# f28069_interfacing.net
KiCad netlist of a schematic drawn in EAGLE
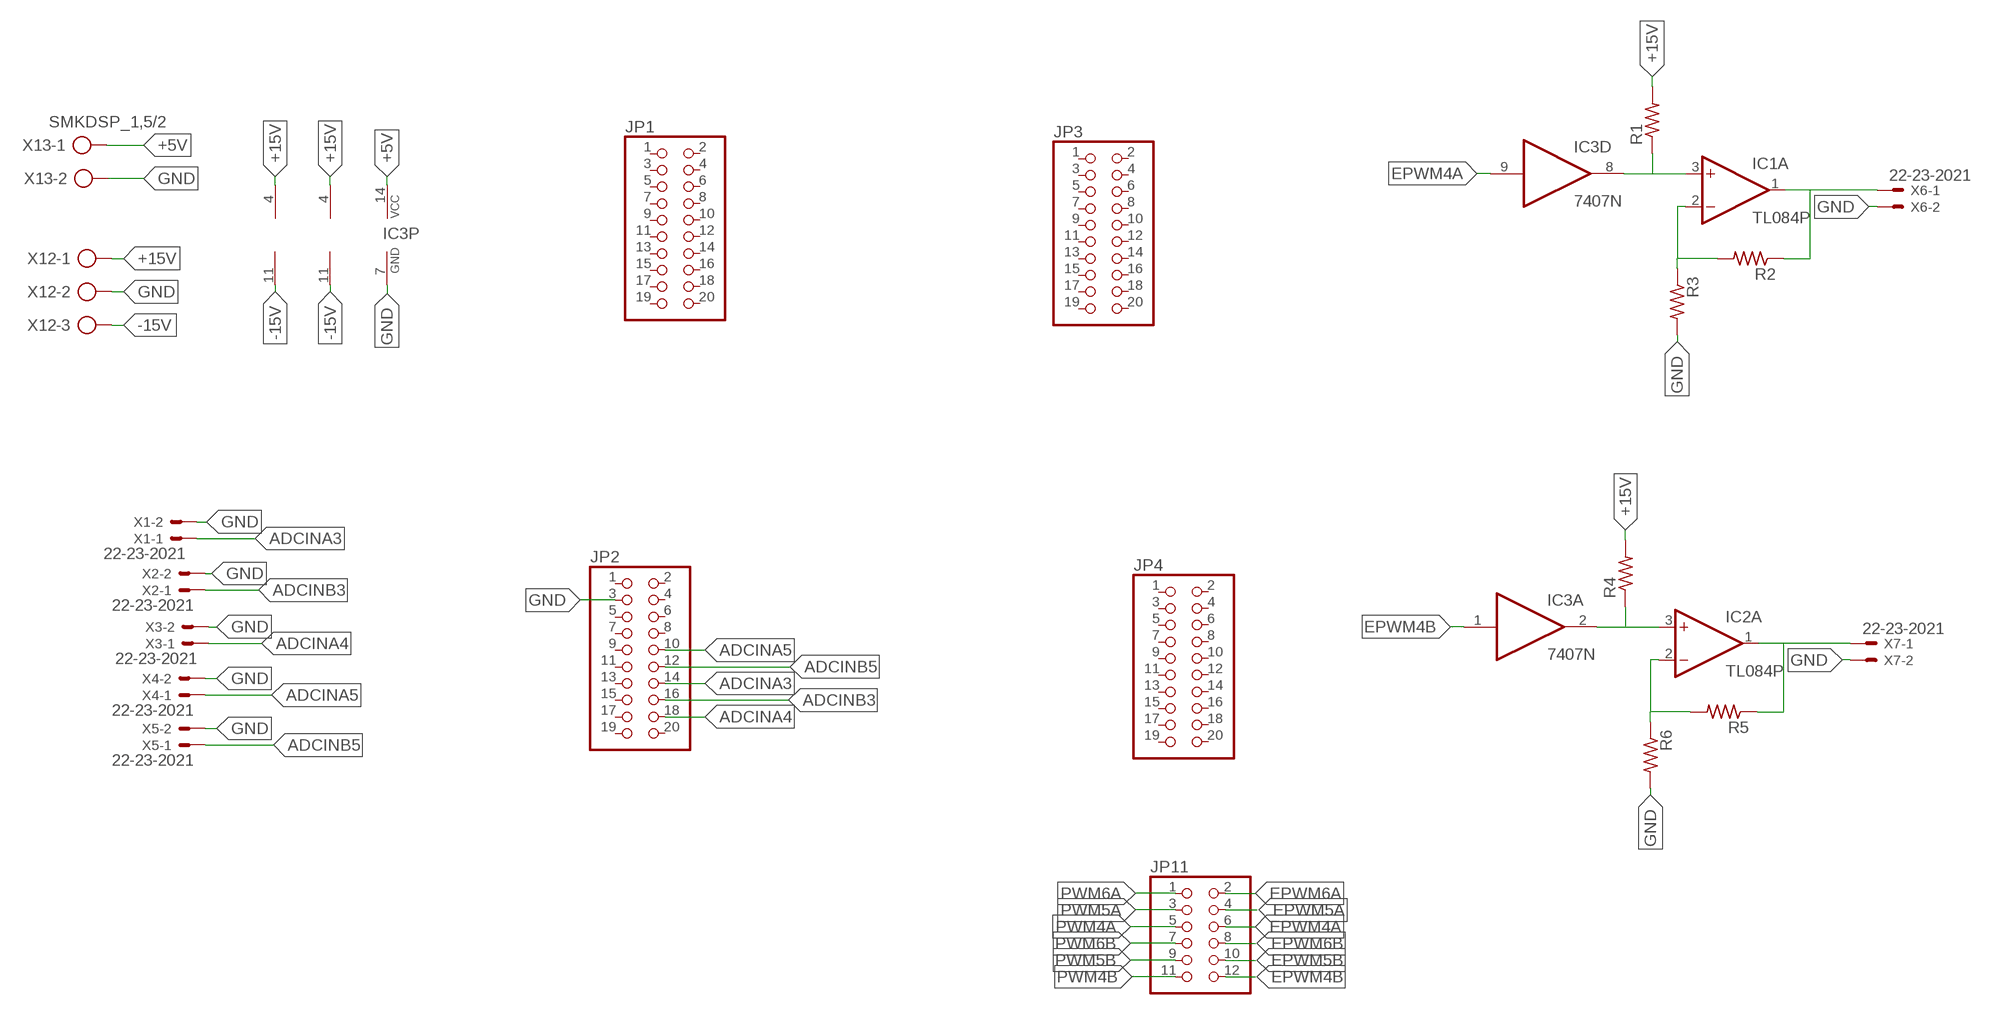
[diagram p0: schematic, sheet 1, part 1 of 2]
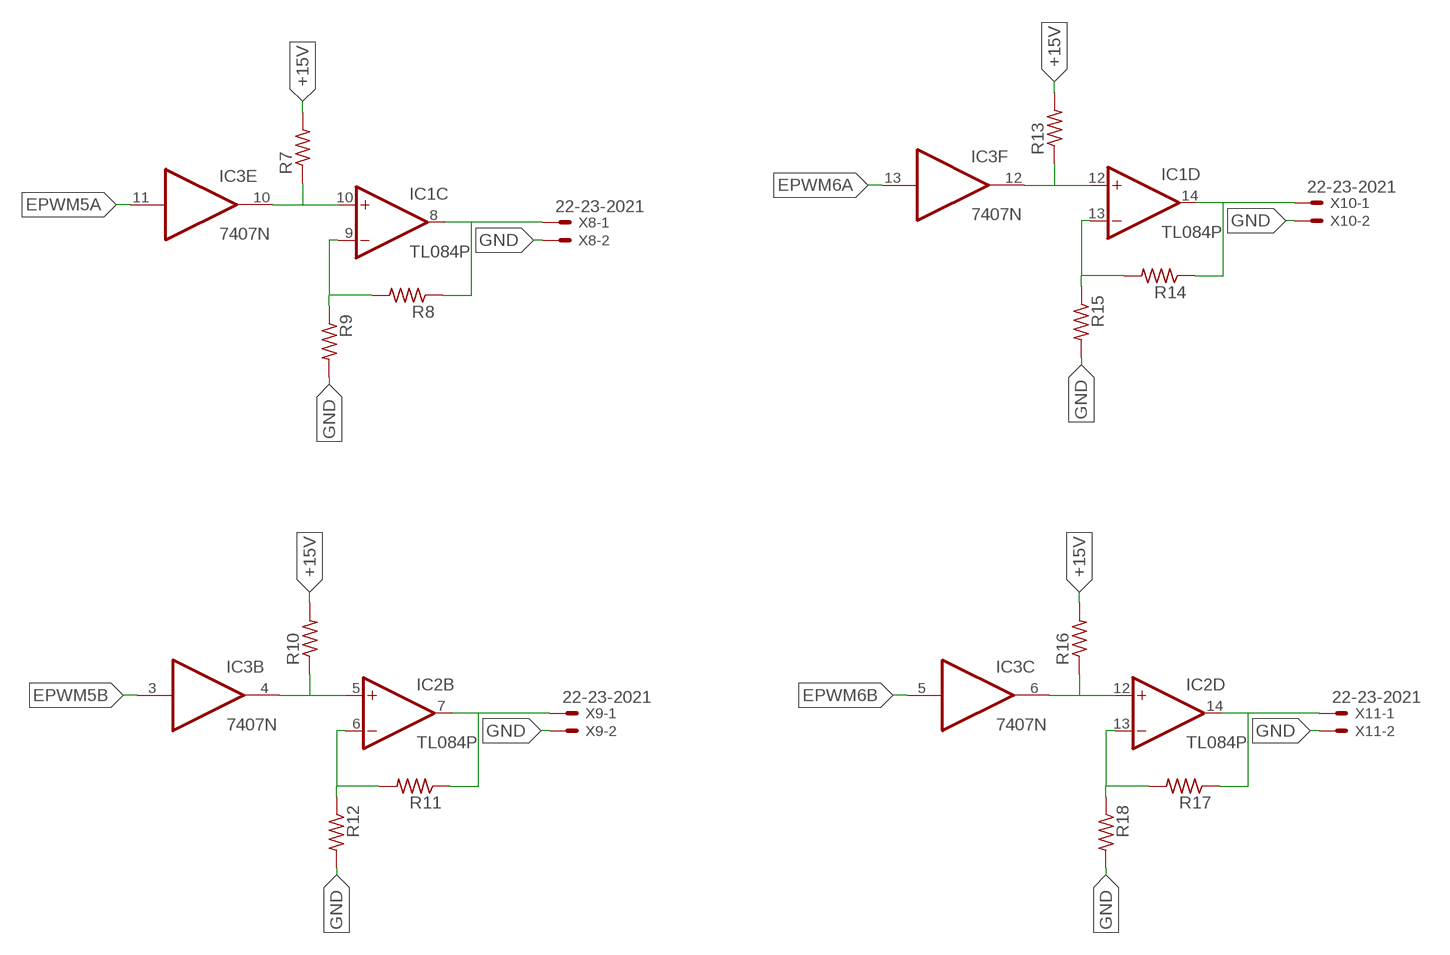
[diagram p1: schematic, sheet 1, part 2 of 2]

(export (version "E")
  (design (tool "Eeschema 10.0.6"))
  (components
    (comp (ref "IC1")
      (value "TL084P")
      (footprint "eagle-import:DIL14")
      (libsource (lib "eagle-import") (part "TL084P"))
    )
    (comp (ref "IC2")
      (value "TL084P")
      (footprint "eagle-import:DIL14")
      (libsource (lib "eagle-import") (part "TL084P"))
    )
    (comp (ref "IC3")
      (value "7407N")
      (footprint "eagle-import:DIL14")
      (libsource (lib "eagle-import") (part "7407N"))
    )
    (comp (ref "JP1")
      (value "PINHD-2X10")
      (footprint "eagle-import:2X10")
      (libsource (lib "eagle-import") (part "PINHD-2X10"))
    )
    (comp (ref "JP2")
      (value "PINHD-2X10")
      (footprint "eagle-import:2X10")
      (libsource (lib "eagle-import") (part "PINHD-2X10"))
    )
    (comp (ref "JP3")
      (value "PINHD-2X10")
      (footprint "eagle-import:2X10")
      (libsource (lib "eagle-import") (part "PINHD-2X10"))
    )
    (comp (ref "JP4")
      (value "PINHD-2X10")
      (footprint "eagle-import:2X10")
      (libsource (lib "eagle-import") (part "PINHD-2X10"))
    )
    (comp (ref "JP11")
      (value "PINHD-2X6")
      (footprint "eagle-import:2X06")
      (libsource (lib "eagle-import") (part "PINHD-2X6"))
    )
    (comp (ref "R1")
      (value "R-US_0207/10")
      (footprint "eagle-import:0207_10")
      (libsource (lib "eagle-import") (part "R-US_0207/10"))
    )
    (comp (ref "R2")
      (value "R-US_0207/10")
      (footprint "eagle-import:0207_10")
      (libsource (lib "eagle-import") (part "R-US_0207/10"))
    )
    (comp (ref "R3")
      (value "R-US_0207/10")
      (footprint "eagle-import:0207_10")
      (libsource (lib "eagle-import") (part "R-US_0207/10"))
    )
    (comp (ref "R4")
      (value "R-US_0207/10")
      (footprint "eagle-import:0207_10")
      (libsource (lib "eagle-import") (part "R-US_0207/10"))
    )
    (comp (ref "R5")
      (value "R-US_0207/10")
      (footprint "eagle-import:0207_10")
      (libsource (lib "eagle-import") (part "R-US_0207/10"))
    )
    (comp (ref "R6")
      (value "R-US_0207/10")
      (footprint "eagle-import:0207_10")
      (libsource (lib "eagle-import") (part "R-US_0207/10"))
    )
    (comp (ref "R7")
      (value "R-US_0207/10")
      (footprint "eagle-import:0207_10")
      (libsource (lib "eagle-import") (part "R-US_0207/10"))
    )
    (comp (ref "R8")
      (value "R-US_0207/10")
      (footprint "eagle-import:0207_10")
      (libsource (lib "eagle-import") (part "R-US_0207/10"))
    )
    (comp (ref "R9")
      (value "R-US_0207/10")
      (footprint "eagle-import:0207_10")
      (libsource (lib "eagle-import") (part "R-US_0207/10"))
    )
    (comp (ref "R10")
      (value "R-US_0207/10")
      (footprint "eagle-import:0207_10")
      (libsource (lib "eagle-import") (part "R-US_0207/10"))
    )
    (comp (ref "R11")
      (value "R-US_0207/10")
      (footprint "eagle-import:0207_10")
      (libsource (lib "eagle-import") (part "R-US_0207/10"))
    )
    (comp (ref "R12")
      (value "R-US_0207/10")
      (footprint "eagle-import:0207_10")
      (libsource (lib "eagle-import") (part "R-US_0207/10"))
    )
    (comp (ref "R13")
      (value "R-US_0207/10")
      (footprint "eagle-import:0207_10")
      (libsource (lib "eagle-import") (part "R-US_0207/10"))
    )
    (comp (ref "R14")
      (value "R-US_0207/10")
      (footprint "eagle-import:0207_10")
      (libsource (lib "eagle-import") (part "R-US_0207/10"))
    )
    (comp (ref "R15")
      (value "R-US_0207/10")
      (footprint "eagle-import:0207_10")
      (libsource (lib "eagle-import") (part "R-US_0207/10"))
    )
    (comp (ref "R16")
      (value "R-US_0207/10")
      (footprint "eagle-import:0207_10")
      (libsource (lib "eagle-import") (part "R-US_0207/10"))
    )
    (comp (ref "R17")
      (value "R-US_0207/10")
      (footprint "eagle-import:0207_10")
      (libsource (lib "eagle-import") (part "R-US_0207/10"))
    )
    (comp (ref "R18")
      (value "R-US_0207/10")
      (footprint "eagle-import:0207_10")
      (libsource (lib "eagle-import") (part "R-US_0207/10"))
    )
    (comp (ref "X1")
      (value "22-23-2021")
      (footprint "eagle-import:22-23-2021")
      (fields (field (name "MF") "MOLEX"))
      (libsource (lib "eagle-import") (part "22-23-2021"))
    )
    (comp (ref "X2")
      (value "22-23-2021")
      (footprint "eagle-import:22-23-2021")
      (fields (field (name "MF") "MOLEX"))
      (libsource (lib "eagle-import") (part "22-23-2021"))
    )
    (comp (ref "X3")
      (value "22-23-2021")
      (footprint "eagle-import:22-23-2021")
      (fields (field (name "MF") "MOLEX"))
      (libsource (lib "eagle-import") (part "22-23-2021"))
    )
    (comp (ref "X4")
      (value "22-23-2021")
      (footprint "eagle-import:22-23-2021")
      (fields (field (name "MF") "MOLEX"))
      (libsource (lib "eagle-import") (part "22-23-2021"))
    )
    (comp (ref "X5")
      (value "22-23-2021")
      (footprint "eagle-import:22-23-2021")
      (fields (field (name "MF") "MOLEX"))
      (libsource (lib "eagle-import") (part "22-23-2021"))
    )
    (comp (ref "X6")
      (value "22-23-2021")
      (footprint "eagle-import:22-23-2021")
      (fields (field (name "MF") "MOLEX"))
      (libsource (lib "eagle-import") (part "22-23-2021"))
    )
    (comp (ref "X7")
      (value "22-23-2021")
      (footprint "eagle-import:22-23-2021")
      (fields (field (name "MF") "MOLEX"))
      (libsource (lib "eagle-import") (part "22-23-2021"))
    )
    (comp (ref "X8")
      (value "22-23-2021")
      (footprint "eagle-import:22-23-2021")
      (fields (field (name "MF") "MOLEX"))
      (libsource (lib "eagle-import") (part "22-23-2021"))
    )
    (comp (ref "X9")
      (value "22-23-2021")
      (footprint "eagle-import:22-23-2021")
      (fields (field (name "MF") "MOLEX"))
      (libsource (lib "eagle-import") (part "22-23-2021"))
    )
    (comp (ref "X10")
      (value "22-23-2021")
      (footprint "eagle-import:22-23-2021")
      (fields (field (name "MF") "MOLEX"))
      (libsource (lib "eagle-import") (part "22-23-2021"))
    )
    (comp (ref "X11")
      (value "22-23-2021")
      (footprint "eagle-import:22-23-2021")
      (fields (field (name "MF") "MOLEX"))
      (libsource (lib "eagle-import") (part "22-23-2021"))
    )
    (comp (ref "X12")
      (value "AK300/3")
      (footprint "eagle-import:AK300_3")
      (libsource (lib "eagle-import") (part "AK300/3"))
    )
    (comp (ref "X13")
      (value "SMKDSP_1,5/2")
      (footprint "eagle-import:SMKDSP_1,5_2")
      (fields (field (name "MF") "FARNELL") (field (name "MPN") "1733570"))
      (libsource (lib "eagle-import") (part "SMKDSP_1,5/2"))
    )
  )
  (nets
    (net (code "1") (name "+5V") (class "Default")
      (node (ref "IC3") (pin "14") (pinfunction "VCC_14") (pintype "power_in"))
      (node (ref "X13") (pin "1") (pinfunction "KL_1") (pintype "passive"))
    )
    (net (code "2") (name "+15V") (class "Default")
      (node (ref "IC1") (pin "4") (pinfunction "V+_4") (pintype "power_in"))
      (node (ref "IC2") (pin "4") (pinfunction "V+_4") (pintype "power_in"))
      (node (ref "R1") (pin "2") (pinfunction "2_2") (pintype "passive"))
      (node (ref "R10") (pin "2") (pinfunction "2_2") (pintype "passive"))
      (node (ref "R13") (pin "2") (pinfunction "2_2") (pintype "passive"))
      (node (ref "R16") (pin "2") (pinfunction "2_2") (pintype "passive"))
      (node (ref "R4") (pin "2") (pinfunction "2_2") (pintype "passive"))
      (node (ref "R7") (pin "2") (pinfunction "2_2") (pintype "passive"))
      (node (ref "X12") (pin "1") (pinfunction "KL_1") (pintype "passive"))
    )
    (net (code "3") (name "-15V") (class "Default")
      (node (ref "IC1") (pin "11") (pinfunction "V-_11") (pintype "power_in"))
      (node (ref "IC2") (pin "11") (pinfunction "V-_11") (pintype "power_in"))
      (node (ref "X12") (pin "3") (pinfunction "KL_3") (pintype "passive"))
    )
    (net (code "4") (name "ADCINA3") (class "Default")
      (node (ref "JP2") (pin "14") (pinfunction "14_14") (pintype "passive"))
      (node (ref "X1") (pin "1") (pinfunction "S_1") (pintype "passive"))
    )
    (net (code "5") (name "ADCINA4") (class "Default")
      (node (ref "JP2") (pin "18") (pinfunction "18_18") (pintype "passive"))
      (node (ref "X3") (pin "1") (pinfunction "S_1") (pintype "passive"))
    )
    (net (code "6") (name "ADCINA5") (class "Default")
      (node (ref "JP2") (pin "10") (pinfunction "10_10") (pintype "passive"))
      (node (ref "X4") (pin "1") (pinfunction "S_1") (pintype "passive"))
    )
    (net (code "7") (name "ADCINB3") (class "Default")
      (node (ref "JP2") (pin "16") (pinfunction "16_16") (pintype "passive"))
      (node (ref "X2") (pin "1") (pinfunction "S_1") (pintype "passive"))
    )
    (net (code "8") (name "ADCINB5") (class "Default")
      (node (ref "JP2") (pin "12") (pinfunction "12_12") (pintype "passive"))
      (node (ref "X5") (pin "1") (pinfunction "S_1") (pintype "passive"))
    )
    (net (code "9") (name "EPWM4A") (class "Default")
      (node (ref "IC3") (pin "9") (pinfunction "I_9") (pintype "input"))
      (node (ref "JP11") (pin "6") (pinfunction "6_6") (pintype "passive"))
    )
    (net (code "10") (name "EPWM4B") (class "Default")
      (node (ref "IC3") (pin "1") (pinfunction "I_1") (pintype "input"))
      (node (ref "JP11") (pin "12") (pinfunction "12_12") (pintype "passive"))
    )
    (net (code "11") (name "EPWM5A") (class "Default")
      (node (ref "IC3") (pin "11") (pinfunction "I_11") (pintype "input"))
      (node (ref "JP11") (pin "4") (pinfunction "4_4") (pintype "passive"))
    )
    (net (code "12") (name "EPWM5B") (class "Default")
      (node (ref "IC3") (pin "3") (pinfunction "I_3") (pintype "input"))
      (node (ref "JP11") (pin "10") (pinfunction "10_10") (pintype "passive"))
    )
    (net (code "13") (name "EPWM6A") (class "Default")
      (node (ref "IC3") (pin "13") (pinfunction "I_13") (pintype "input"))
      (node (ref "JP11") (pin "2") (pinfunction "2_2") (pintype "passive"))
    )
    (net (code "14") (name "EPWM6B") (class "Default")
      (node (ref "IC3") (pin "5") (pinfunction "I_5") (pintype "input"))
      (node (ref "JP11") (pin "8") (pinfunction "8_8") (pintype "passive"))
    )
    (net (code "15") (name "GND") (class "Default")
      (node (ref "IC3") (pin "7") (pinfunction "GND_7") (pintype "power_in"))
      (node (ref "JP2") (pin "3") (pinfunction "3_3") (pintype "passive"))
      (node (ref "R12") (pin "2") (pinfunction "2_2") (pintype "passive"))
      (node (ref "R15") (pin "2") (pinfunction "2_2") (pintype "passive"))
      (node (ref "R18") (pin "2") (pinfunction "2_2") (pintype "passive"))
      (node (ref "R3") (pin "2") (pinfunction "2_2") (pintype "passive"))
      (node (ref "R6") (pin "2") (pinfunction "2_2") (pintype "passive"))
      (node (ref "R9") (pin "2") (pinfunction "2_2") (pintype "passive"))
      (node (ref "X1") (pin "2") (pinfunction "S_2") (pintype "passive"))
      (node (ref "X10") (pin "2") (pinfunction "S_2") (pintype "passive"))
      (node (ref "X11") (pin "2") (pinfunction "S_2") (pintype "passive"))
      (node (ref "X12") (pin "2") (pinfunction "KL_2") (pintype "passive"))
      (node (ref "X13") (pin "2") (pinfunction "KL_2") (pintype "passive"))
      (node (ref "X2") (pin "2") (pinfunction "S_2") (pintype "passive"))
      (node (ref "X3") (pin "2") (pinfunction "S_2") (pintype "passive"))
      (node (ref "X4") (pin "2") (pinfunction "S_2") (pintype "passive"))
      (node (ref "X5") (pin "2") (pinfunction "S_2") (pintype "passive"))
      (node (ref "X6") (pin "2") (pinfunction "S_2") (pintype "passive"))
      (node (ref "X7") (pin "2") (pinfunction "S_2") (pintype "passive"))
      (node (ref "X8") (pin "2") (pinfunction "S_2") (pintype "passive"))
      (node (ref "X9") (pin "2") (pinfunction "S_2") (pintype "passive"))
    )
    (net (code "16") (name "Net-(IC1A-+IN)") (class "Default")
      (node (ref "IC1") (pin "3") (pinfunction "+IN_3") (pintype "input"))
      (node (ref "IC3") (pin "8") (pinfunction "O_8") (pintype "open_collector"))
      (node (ref "R1") (pin "1") (pinfunction "1_1") (pintype "passive"))
    )
    (net (code "17") (name "Net-(IC1A--IN)") (class "Default")
      (node (ref "IC1") (pin "2") (pinfunction "-IN_2") (pintype "input"))
      (node (ref "R2") (pin "2") (pinfunction "2_2") (pintype "passive"))
      (node (ref "R3") (pin "1") (pinfunction "1_1") (pintype "passive"))
    )
    (net (code "18") (name "Net-(IC1A-OUT)") (class "Default")
      (node (ref "IC1") (pin "1") (pinfunction "OUT_1") (pintype "output"))
      (node (ref "R2") (pin "1") (pinfunction "1_1") (pintype "passive"))
      (node (ref "X6") (pin "1") (pinfunction "S_1") (pintype "passive"))
    )
    (net (code "19") (name "Net-(IC1C-+IN)") (class "Default")
      (node (ref "IC1") (pin "10") (pinfunction "+IN_10") (pintype "input"))
      (node (ref "IC3") (pin "10") (pinfunction "O_10") (pintype "open_collector"))
      (node (ref "R7") (pin "1") (pinfunction "1_1") (pintype "passive"))
    )
    (net (code "20") (name "Net-(IC1C--IN)") (class "Default")
      (node (ref "IC1") (pin "9") (pinfunction "-IN_9") (pintype "input"))
      (node (ref "R8") (pin "2") (pinfunction "2_2") (pintype "passive"))
      (node (ref "R9") (pin "1") (pinfunction "1_1") (pintype "passive"))
    )
    (net (code "21") (name "Net-(IC1C-OUT)") (class "Default")
      (node (ref "IC1") (pin "8") (pinfunction "OUT_8") (pintype "output"))
      (node (ref "R8") (pin "1") (pinfunction "1_1") (pintype "passive"))
      (node (ref "X8") (pin "1") (pinfunction "S_1") (pintype "passive"))
    )
    (net (code "22") (name "Net-(IC1D-+IN)") (class "Default")
      (node (ref "IC1") (pin "12") (pinfunction "+IN_12") (pintype "input"))
      (node (ref "IC3") (pin "12") (pinfunction "O_12") (pintype "open_collector"))
      (node (ref "R13") (pin "1") (pinfunction "1_1") (pintype "passive"))
    )
    (net (code "23") (name "Net-(IC1D--IN)") (class "Default")
      (node (ref "IC1") (pin "13") (pinfunction "-IN_13") (pintype "input"))
      (node (ref "R14") (pin "2") (pinfunction "2_2") (pintype "passive"))
      (node (ref "R15") (pin "1") (pinfunction "1_1") (pintype "passive"))
    )
    (net (code "24") (name "Net-(IC1D-OUT)") (class "Default")
      (node (ref "IC1") (pin "14") (pinfunction "OUT_14") (pintype "output"))
      (node (ref "R14") (pin "1") (pinfunction "1_1") (pintype "passive"))
      (node (ref "X10") (pin "1") (pinfunction "S_1") (pintype "passive"))
    )
    (net (code "25") (name "Net-(IC2A-+IN)") (class "Default")
      (node (ref "IC2") (pin "3") (pinfunction "+IN_3") (pintype "input"))
      (node (ref "IC3") (pin "2") (pinfunction "O_2") (pintype "open_collector"))
      (node (ref "R4") (pin "1") (pinfunction "1_1") (pintype "passive"))
    )
    (net (code "26") (name "Net-(IC2A--IN)") (class "Default")
      (node (ref "IC2") (pin "2") (pinfunction "-IN_2") (pintype "input"))
      (node (ref "R5") (pin "2") (pinfunction "2_2") (pintype "passive"))
      (node (ref "R6") (pin "1") (pinfunction "1_1") (pintype "passive"))
    )
    (net (code "27") (name "Net-(IC2A-OUT)") (class "Default")
      (node (ref "IC2") (pin "1") (pinfunction "OUT_1") (pintype "output"))
      (node (ref "R5") (pin "1") (pinfunction "1_1") (pintype "passive"))
      (node (ref "X7") (pin "1") (pinfunction "S_1") (pintype "passive"))
    )
    (net (code "28") (name "Net-(IC2B-+IN)") (class "Default")
      (node (ref "IC2") (pin "5") (pinfunction "+IN_5") (pintype "input"))
      (node (ref "IC3") (pin "4") (pinfunction "O_4") (pintype "open_collector"))
      (node (ref "R10") (pin "1") (pinfunction "1_1") (pintype "passive"))
    )
    (net (code "29") (name "Net-(IC2B--IN)") (class "Default")
      (node (ref "IC2") (pin "6") (pinfunction "-IN_6") (pintype "input"))
      (node (ref "R11") (pin "2") (pinfunction "2_2") (pintype "passive"))
      (node (ref "R12") (pin "1") (pinfunction "1_1") (pintype "passive"))
    )
    (net (code "30") (name "Net-(IC2B-OUT)") (class "Default")
      (node (ref "IC2") (pin "7") (pinfunction "OUT_7") (pintype "output"))
      (node (ref "R11") (pin "1") (pinfunction "1_1") (pintype "passive"))
      (node (ref "X9") (pin "1") (pinfunction "S_1") (pintype "passive"))
    )
    (net (code "31") (name "Net-(IC2D-+IN)") (class "Default")
      (node (ref "IC2") (pin "12") (pinfunction "+IN_12") (pintype "input"))
      (node (ref "IC3") (pin "6") (pinfunction "O_6") (pintype "open_collector"))
      (node (ref "R16") (pin "1") (pinfunction "1_1") (pintype "passive"))
    )
    (net (code "32") (name "Net-(IC2D--IN)") (class "Default")
      (node (ref "IC2") (pin "13") (pinfunction "-IN_13") (pintype "input"))
      (node (ref "R17") (pin "2") (pinfunction "2_2") (pintype "passive"))
      (node (ref "R18") (pin "1") (pinfunction "1_1") (pintype "passive"))
    )
    (net (code "33") (name "Net-(IC2D-OUT)") (class "Default")
      (node (ref "IC2") (pin "14") (pinfunction "OUT_14") (pintype "output"))
      (node (ref "R17") (pin "1") (pinfunction "1_1") (pintype "passive"))
      (node (ref "X11") (pin "1") (pinfunction "S_1") (pintype "passive"))
    )
    (net (code "34") (name "PWM4A") (class "Default")
      (node (ref "JP11") (pin "5") (pinfunction "5_5") (pintype "passive"))
    )
    (net (code "35") (name "PWM4B") (class "Default")
      (node (ref "JP11") (pin "11") (pinfunction "11_11") (pintype "passive"))
    )
    (net (code "36") (name "PWM5A") (class "Default")
      (node (ref "JP11") (pin "3") (pinfunction "3_3") (pintype "passive"))
    )
    (net (code "37") (name "PWM5B") (class "Default")
      (node (ref "JP11") (pin "9") (pinfunction "9_9") (pintype "passive"))
    )
    (net (code "38") (name "PWM6A") (class "Default")
      (node (ref "JP11") (pin "1") (pinfunction "1_1") (pintype "passive"))
    )
    (net (code "39") (name "PWM6B") (class "Default")
      (node (ref "JP11") (pin "7") (pinfunction "7_7") (pintype "passive"))
    )
    (net (code "40") (name "unconnected-(JP1-Pad1)") (class "Default")
      (node (ref "JP1") (pin "1") (pinfunction "1_1") (pintype "passive"))
    )
    (net (code "41") (name "unconnected-(JP1-Pad2)") (class "Default")
      (node (ref "JP1") (pin "2") (pinfunction "2_2") (pintype "passive"))
    )
    (net (code "42") (name "unconnected-(JP1-Pad3)") (class "Default")
      (node (ref "JP1") (pin "3") (pinfunction "3_3") (pintype "passive"))
    )
    (net (code "43") (name "unconnected-(JP1-Pad4)") (class "Default")
      (node (ref "JP1") (pin "4") (pinfunction "4_4") (pintype "passive"))
    )
    (net (code "44") (name "unconnected-(JP1-Pad5)") (class "Default")
      (node (ref "JP1") (pin "5") (pinfunction "5_5") (pintype "passive"))
    )
    (net (code "45") (name "unconnected-(JP1-Pad6)") (class "Default")
      (node (ref "JP1") (pin "6") (pinfunction "6_6") (pintype "passive"))
    )
    (net (code "46") (name "unconnected-(JP1-Pad7)") (class "Default")
      (node (ref "JP1") (pin "7") (pinfunction "7_7") (pintype "passive"))
    )
    (net (code "47") (name "unconnected-(JP1-Pad8)") (class "Default")
      (node (ref "JP1") (pin "8") (pinfunction "8_8") (pintype "passive"))
    )
    (net (code "48") (name "unconnected-(JP1-Pad9)") (class "Default")
      (node (ref "JP1") (pin "9") (pinfunction "9_9") (pintype "passive"))
    )
    (net (code "49") (name "unconnected-(JP1-Pad10)") (class "Default")
      (node (ref "JP1") (pin "10") (pinfunction "10_10") (pintype "passive"))
    )
    (net (code "50") (name "unconnected-(JP1-Pad11)") (class "Default")
      (node (ref "JP1") (pin "11") (pinfunction "11_11") (pintype "passive"))
    )
    (net (code "51") (name "unconnected-(JP1-Pad12)") (class "Default")
      (node (ref "JP1") (pin "12") (pinfunction "12_12") (pintype "passive"))
    )
    (net (code "52") (name "unconnected-(JP1-Pad13)") (class "Default")
      (node (ref "JP1") (pin "13") (pinfunction "13_13") (pintype "passive"))
    )
    (net (code "53") (name "unconnected-(JP1-Pad14)") (class "Default")
      (node (ref "JP1") (pin "14") (pinfunction "14_14") (pintype "passive"))
    )
    (net (code "54") (name "unconnected-(JP1-Pad15)") (class "Default")
      (node (ref "JP1") (pin "15") (pinfunction "15_15") (pintype "passive"))
    )
    (net (code "55") (name "unconnected-(JP1-Pad16)") (class "Default")
      (node (ref "JP1") (pin "16") (pinfunction "16_16") (pintype "passive"))
    )
    (net (code "56") (name "unconnected-(JP1-Pad17)") (class "Default")
      (node (ref "JP1") (pin "17") (pinfunction "17_17") (pintype "passive"))
    )
    (net (code "57") (name "unconnected-(JP1-Pad18)") (class "Default")
      (node (ref "JP1") (pin "18") (pinfunction "18_18") (pintype "passive"))
    )
    (net (code "58") (name "unconnected-(JP1-Pad19)") (class "Default")
      (node (ref "JP1") (pin "19") (pinfunction "19_19") (pintype "passive"))
    )
    (net (code "59") (name "unconnected-(JP1-Pad20)") (class "Default")
      (node (ref "JP1") (pin "20") (pinfunction "20_20") (pintype "passive"))
    )
    (net (code "60") (name "unconnected-(JP2-Pad1)") (class "Default")
      (node (ref "JP2") (pin "1") (pinfunction "1_1") (pintype "passive"))
    )
    (net (code "61") (name "unconnected-(JP2-Pad2)") (class "Default")
      (node (ref "JP2") (pin "2") (pinfunction "2_2") (pintype "passive"))
    )
    (net (code "62") (name "unconnected-(JP2-Pad4)") (class "Default")
      (node (ref "JP2") (pin "4") (pinfunction "4_4") (pintype "passive"))
    )
    (net (code "63") (name "unconnected-(JP2-Pad5)") (class "Default")
      (node (ref "JP2") (pin "5") (pinfunction "5_5") (pintype "passive"))
    )
    (net (code "64") (name "unconnected-(JP2-Pad6)") (class "Default")
      (node (ref "JP2") (pin "6") (pinfunction "6_6") (pintype "passive"))
    )
    (net (code "65") (name "unconnected-(JP2-Pad7)") (class "Default")
      (node (ref "JP2") (pin "7") (pinfunction "7_7") (pintype "passive"))
    )
    (net (code "66") (name "unconnected-(JP2-Pad8)") (class "Default")
      (node (ref "JP2") (pin "8") (pinfunction "8_8") (pintype "passive"))
    )
    (net (code "67") (name "unconnected-(JP2-Pad9)") (class "Default")
      (node (ref "JP2") (pin "9") (pinfunction "9_9") (pintype "passive"))
    )
    (net (code "68") (name "unconnected-(JP2-Pad11)") (class "Default")
      (node (ref "JP2") (pin "11") (pinfunction "11_11") (pintype "passive"))
    )
    (net (code "69") (name "unconnected-(JP2-Pad13)") (class "Default")
      (node (ref "JP2") (pin "13") (pinfunction "13_13") (pintype "passive"))
    )
    (net (code "70") (name "unconnected-(JP2-Pad15)") (class "Default")
      (node (ref "JP2") (pin "15") (pinfunction "15_15") (pintype "passive"))
    )
    (net (code "71") (name "unconnected-(JP2-Pad17)") (class "Default")
      (node (ref "JP2") (pin "17") (pinfunction "17_17") (pintype "passive"))
    )
    (net (code "72") (name "unconnected-(JP2-Pad19)") (class "Default")
      (node (ref "JP2") (pin "19") (pinfunction "19_19") (pintype "passive"))
    )
    (net (code "73") (name "unconnected-(JP2-Pad20)") (class "Default")
      (node (ref "JP2") (pin "20") (pinfunction "20_20") (pintype "passive"))
    )
    (net (code "74") (name "unconnected-(JP3-Pad1)") (class "Default")
      (node (ref "JP3") (pin "1") (pinfunction "1_1") (pintype "passive"))
    )
    (net (code "75") (name "unconnected-(JP3-Pad2)") (class "Default")
      (node (ref "JP3") (pin "2") (pinfunction "2_2") (pintype "passive"))
    )
    (net (code "76") (name "unconnected-(JP3-Pad3)") (class "Default")
      (node (ref "JP3") (pin "3") (pinfunction "3_3") (pintype "passive"))
    )
    (net (code "77") (name "unconnected-(JP3-Pad4)") (class "Default")
      (node (ref "JP3") (pin "4") (pinfunction "4_4") (pintype "passive"))
    )
    (net (code "78") (name "unconnected-(JP3-Pad5)") (class "Default")
      (node (ref "JP3") (pin "5") (pinfunction "5_5") (pintype "passive"))
    )
    (net (code "79") (name "unconnected-(JP3-Pad6)") (class "Default")
      (node (ref "JP3") (pin "6") (pinfunction "6_6") (pintype "passive"))
    )
    (net (code "80") (name "unconnected-(JP3-Pad7)") (class "Default")
      (node (ref "JP3") (pin "7") (pinfunction "7_7") (pintype "passive"))
    )
    (net (code "81") (name "unconnected-(JP3-Pad8)") (class "Default")
      (node (ref "JP3") (pin "8") (pinfunction "8_8") (pintype "passive"))
    )
    (net (code "82") (name "unconnected-(JP3-Pad9)") (class "Default")
      (node (ref "JP3") (pin "9") (pinfunction "9_9") (pintype "passive"))
    )
    (net (code "83") (name "unconnected-(JP3-Pad10)") (class "Default")
      (node (ref "JP3") (pin "10") (pinfunction "10_10") (pintype "passive"))
    )
    (net (code "84") (name "unconnected-(JP3-Pad11)") (class "Default")
      (node (ref "JP3") (pin "11") (pinfunction "11_11") (pintype "passive"))
    )
    (net (code "85") (name "unconnected-(JP3-Pad12)") (class "Default")
      (node (ref "JP3") (pin "12") (pinfunction "12_12") (pintype "passive"))
    )
    (net (code "86") (name "unconnected-(JP3-Pad13)") (class "Default")
      (node (ref "JP3") (pin "13") (pinfunction "13_13") (pintype "passive"))
    )
    (net (code "87") (name "unconnected-(JP3-Pad14)") (class "Default")
      (node (ref "JP3") (pin "14") (pinfunction "14_14") (pintype "passive"))
    )
    (net (code "88") (name "unconnected-(JP3-Pad15)") (class "Default")
      (node (ref "JP3") (pin "15") (pinfunction "15_15") (pintype "passive"))
    )
    (net (code "89") (name "unconnected-(JP3-Pad16)") (class "Default")
      (node (ref "JP3") (pin "16") (pinfunction "16_16") (pintype "passive"))
    )
    (net (code "90") (name "unconnected-(JP3-Pad17)") (class "Default")
      (node (ref "JP3") (pin "17") (pinfunction "17_17") (pintype "passive"))
    )
    (net (code "91") (name "unconnected-(JP3-Pad18)") (class "Default")
      (node (ref "JP3") (pin "18") (pinfunction "18_18") (pintype "passive"))
    )
    (net (code "92") (name "unconnected-(JP3-Pad19)") (class "Default")
      (node (ref "JP3") (pin "19") (pinfunction "19_19") (pintype "passive"))
    )
    (net (code "93") (name "unconnected-(JP3-Pad20)") (class "Default")
      (node (ref "JP3") (pin "20") (pinfunction "20_20") (pintype "passive"))
    )
    (net (code "94") (name "unconnected-(JP4-Pad1)") (class "Default")
      (node (ref "JP4") (pin "1") (pinfunction "1_1") (pintype "passive"))
    )
    (net (code "95") (name "unconnected-(JP4-Pad2)") (class "Default")
      (node (ref "JP4") (pin "2") (pinfunction "2_2") (pintype "passive"))
    )
    (net (code "96") (name "unconnected-(JP4-Pad3)") (class "Default")
      (node (ref "JP4") (pin "3") (pinfunction "3_3") (pintype "passive"))
    )
    (net (code "97") (name "unconnected-(JP4-Pad4)") (class "Default")
      (node (ref "JP4") (pin "4") (pinfunction "4_4") (pintype "passive"))
    )
    (net (code "98") (name "unconnected-(JP4-Pad5)") (class "Default")
      (node (ref "JP4") (pin "5") (pinfunction "5_5") (pintype "passive"))
    )
    (net (code "99") (name "unconnected-(JP4-Pad6)") (class "Default")
      (node (ref "JP4") (pin "6") (pinfunction "6_6") (pintype "passive"))
    )
    (net (code "100") (name "unconnected-(JP4-Pad7)") (class "Default")
      (node (ref "JP4") (pin "7") (pinfunction "7_7") (pintype "passive"))
    )
    (net (code "101") (name "unconnected-(JP4-Pad8)") (class "Default")
      (node (ref "JP4") (pin "8") (pinfunction "8_8") (pintype "passive"))
    )
    (net (code "102") (name "unconnected-(JP4-Pad9)") (class "Default")
      (node (ref "JP4") (pin "9") (pinfunction "9_9") (pintype "passive"))
    )
    (net (code "103") (name "unconnected-(JP4-Pad10)") (class "Default")
      (node (ref "JP4") (pin "10") (pinfunction "10_10") (pintype "passive"))
    )
    (net (code "104") (name "unconnected-(JP4-Pad11)") (class "Default")
      (node (ref "JP4") (pin "11") (pinfunction "11_11") (pintype "passive"))
    )
    (net (code "105") (name "unconnected-(JP4-Pad12)") (class "Default")
      (node (ref "JP4") (pin "12") (pinfunction "12_12") (pintype "passive"))
    )
    (net (code "106") (name "unconnected-(JP4-Pad13)") (class "Default")
      (node (ref "JP4") (pin "13") (pinfunction "13_13") (pintype "passive"))
    )
    (net (code "107") (name "unconnected-(JP4-Pad14)") (class "Default")
      (node (ref "JP4") (pin "14") (pinfunction "14_14") (pintype "passive"))
    )
    (net (code "108") (name "unconnected-(JP4-Pad15)") (class "Default")
      (node (ref "JP4") (pin "15") (pinfunction "15_15") (pintype "passive"))
    )
    (net (code "109") (name "unconnected-(JP4-Pad16)") (class "Default")
      (node (ref "JP4") (pin "16") (pinfunction "16_16") (pintype "passive"))
    )
    (net (code "110") (name "unconnected-(JP4-Pad17)") (class "Default")
      (node (ref "JP4") (pin "17") (pinfunction "17_17") (pintype "passive"))
    )
    (net (code "111") (name "unconnected-(JP4-Pad18)") (class "Default")
      (node (ref "JP4") (pin "18") (pinfunction "18_18") (pintype "passive"))
    )
    (net (code "112") (name "unconnected-(JP4-Pad19)") (class "Default")
      (node (ref "JP4") (pin "19") (pinfunction "19_19") (pintype "passive"))
    )
    (net (code "113") (name "unconnected-(JP4-Pad20)") (class "Default")
      (node (ref "JP4") (pin "20") (pinfunction "20_20") (pintype "passive"))
    )
  )
)
